# OakyWing-v0_2.net
KiCad netlist of a schematic drawn in EAGLE
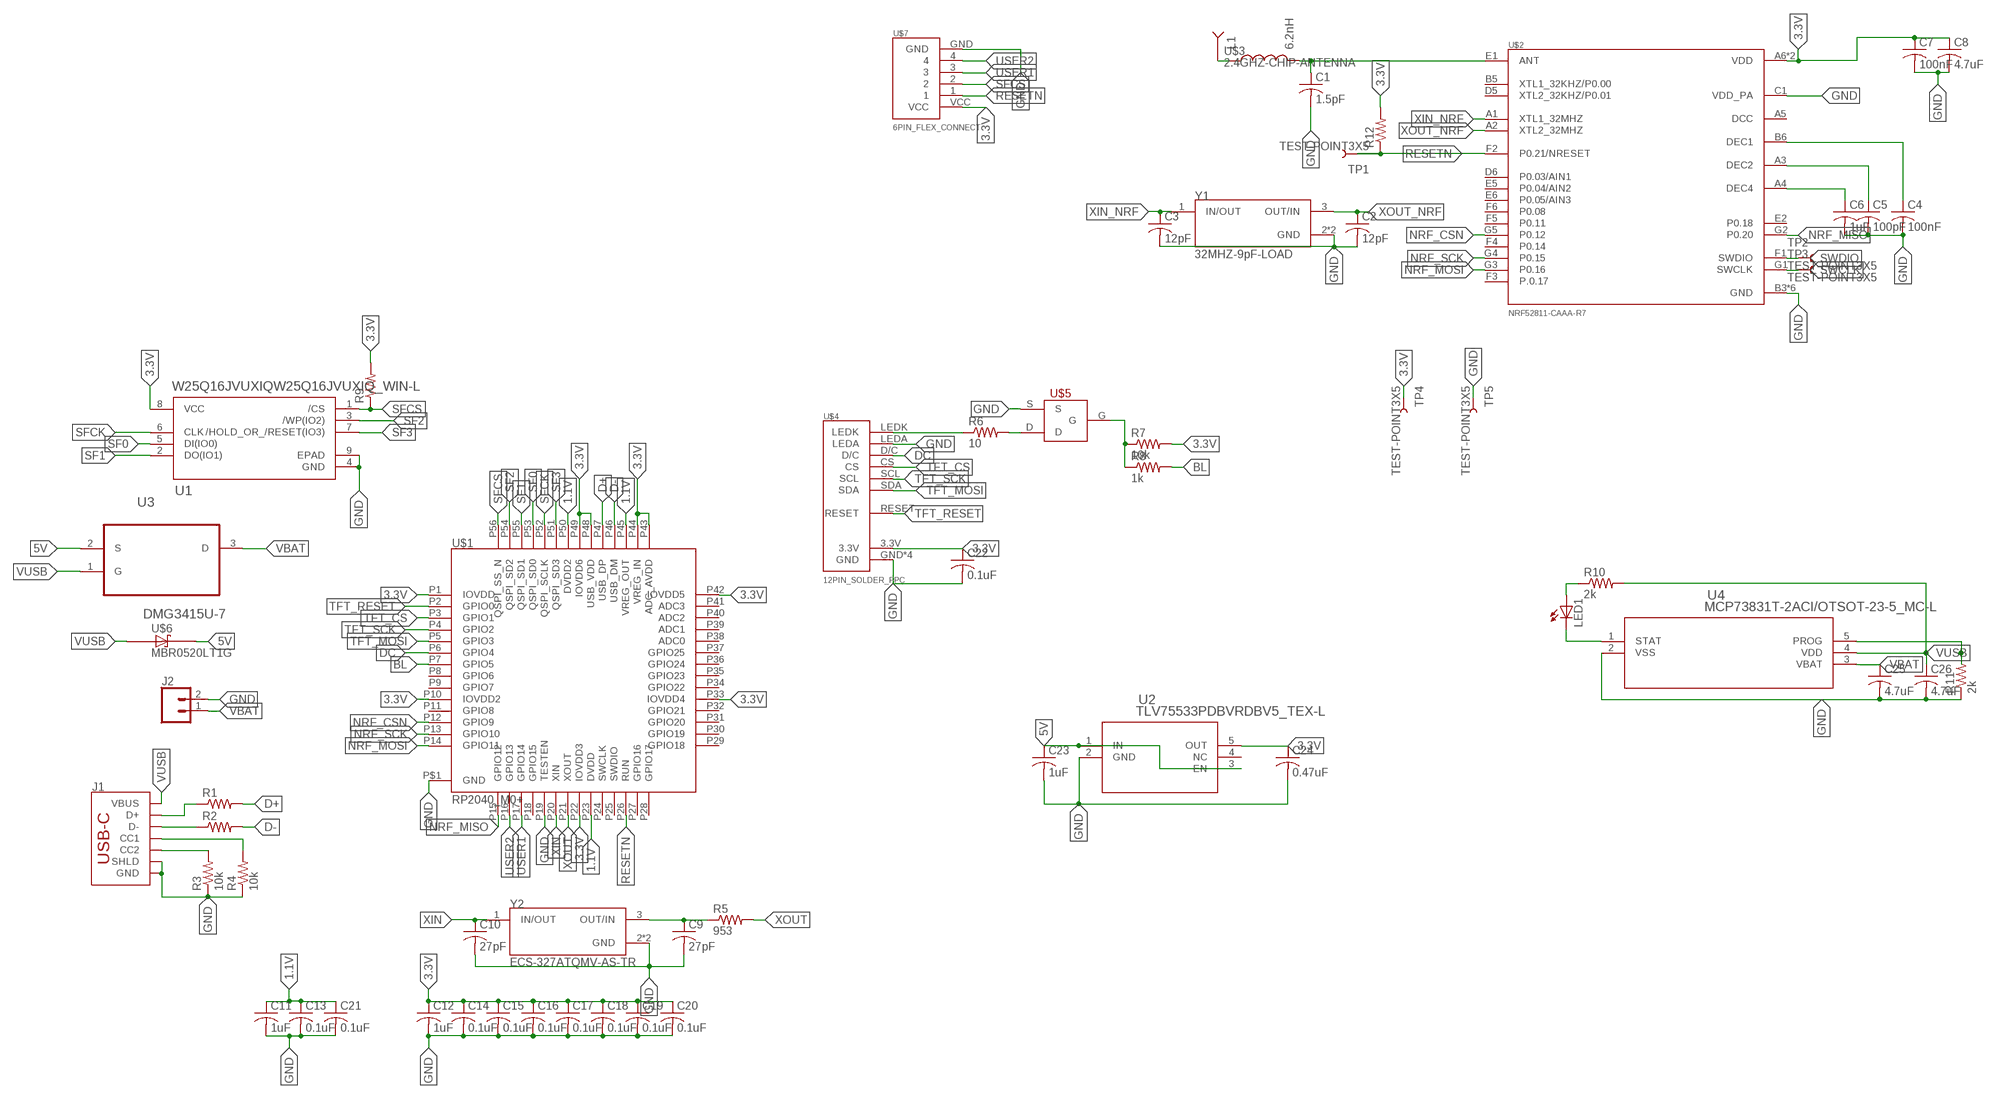
[diagram p0: schematic, sheet 1]

(export (version "E")
  (design (tool "Eeschema 10.0.6"))
  (components
    (comp (ref "C1")
      (value "1.5pF")
      (footprint "eagle-import:C0402")
      (libsource (lib "eagle-import") (part "rcl_334_C-USC0402"))
    )
    (comp (ref "C2")
      (value "12pF")
      (footprint "eagle-import:C0402")
      (libsource (lib "eagle-import") (part "rcl_334_C-USC0402"))
    )
    (comp (ref "C3")
      (value "12pF")
      (footprint "eagle-import:C0402")
      (libsource (lib "eagle-import") (part "C-USC0402"))
    )
    (comp (ref "C4")
      (value "100nF")
      (footprint "eagle-import:C0402")
      (libsource (lib "eagle-import") (part "rcl_334_C-USC0402"))
    )
    (comp (ref "C5")
      (value "100pF")
      (footprint "eagle-import:C0402")
      (libsource (lib "eagle-import") (part "rcl_334_C-USC0402"))
    )
    (comp (ref "C6")
      (value "1uF")
      (footprint "eagle-import:C0402")
      (libsource (lib "eagle-import") (part "rcl_334_C-USC0402"))
    )
    (comp (ref "C7")
      (value "100nF")
      (footprint "eagle-import:C0402")
      (libsource (lib "eagle-import") (part "rcl_334_C-USC0402"))
    )
    (comp (ref "C8")
      (value "4.7uF")
      (footprint "eagle-import:C0603")
      (libsource (lib "eagle-import") (part "rcl_334_C-USC0603"))
    )
    (comp (ref "C9")
      (value "27pF")
      (footprint "eagle-import:C0402")
      (libsource (lib "eagle-import") (part "C-USC0402"))
    )
    (comp (ref "C10")
      (value "27pF")
      (footprint "eagle-import:C0402")
      (libsource (lib "eagle-import") (part "C-USC0402"))
    )
    (comp (ref "C11")
      (value "1uF")
      (footprint "eagle-import:C0402")
      (libsource (lib "eagle-import") (part "C-USC0402"))
    )
    (comp (ref "C12")
      (value "1uF")
      (footprint "eagle-import:C0402")
      (libsource (lib "eagle-import") (part "C-USC0402"))
    )
    (comp (ref "C13")
      (value "0.1uF")
      (footprint "eagle-import:C0402")
      (libsource (lib "eagle-import") (part "C-USC0402"))
    )
    (comp (ref "C14")
      (value "0.1uF")
      (footprint "eagle-import:C0402")
      (libsource (lib "eagle-import") (part "C-USC0402"))
    )
    (comp (ref "C15")
      (value "0.1uF")
      (footprint "eagle-import:C0402")
      (libsource (lib "eagle-import") (part "C-USC0402"))
    )
    (comp (ref "C16")
      (value "0.1uF")
      (footprint "eagle-import:C0402")
      (libsource (lib "eagle-import") (part "C-USC0402"))
    )
    (comp (ref "C17")
      (value "0.1uF")
      (footprint "eagle-import:C0402")
      (libsource (lib "eagle-import") (part "C-USC0402"))
    )
    (comp (ref "C18")
      (value "0.1uF")
      (footprint "eagle-import:C0402")
      (libsource (lib "eagle-import") (part "C-USC0402"))
    )
    (comp (ref "C19")
      (value "0.1uF")
      (footprint "eagle-import:C0402")
      (libsource (lib "eagle-import") (part "C-USC0402"))
    )
    (comp (ref "C20")
      (value "0.1uF")
      (footprint "eagle-import:C0402")
      (libsource (lib "eagle-import") (part "C-USC0402"))
    )
    (comp (ref "C21")
      (value "0.1uF")
      (footprint "eagle-import:C0402")
      (libsource (lib "eagle-import") (part "C-USC0402"))
    )
    (comp (ref "C22")
      (value "0.1uF")
      (footprint "eagle-import:C0402")
      (libsource (lib "eagle-import") (part "rcl_334_C-USC0402"))
    )
    (comp (ref "C23")
      (value "1uF")
      (footprint "eagle-import:C0402")
      (libsource (lib "eagle-import") (part "rcl_334_C-USC0402"))
    )
    (comp (ref "C24")
      (value "0.47uF")
      (footprint "eagle-import:C0402")
      (libsource (lib "eagle-import") (part "rcl_334_C-USC0402"))
    )
    (comp (ref "C25")
      (value "4.7uF")
      (footprint "eagle-import:C0603")
      (libsource (lib "eagle-import") (part "rcl_334_C-USC0603"))
    )
    (comp (ref "C26")
      (value "4.7uF")
      (footprint "eagle-import:C0603")
      (libsource (lib "eagle-import") (part "rcl_334_C-USC0603"))
    )
    (comp (ref "J1")
      (value "USB_C_2-LAYER_PADS")
      (footprint "eagle-import:USB-C-16P-2LAYER-PADS")
      (libsource (lib "eagle-import") (part "USB_C_2-LAYER_PADS"))
    )
    (comp (ref "J2")
      (value "CONN_02")
      (footprint "eagle-import:1X02")
      (libsource (lib "eagle-import") (part "CONN_02"))
    )
    (comp (ref "L1")
      (value "6.2nH")
      (footprint "eagle-import:R0402")
      (libsource (lib "eagle-import") (part "INDUCTOR"))
    )
    (comp (ref "LED1")
      (value "LEDCHIP-LED0603")
      (footprint "eagle-import:CHIP-LED0603")
      (libsource (lib "eagle-import") (part "LEDCHIP-LED0603"))
    )
    (comp (ref "R1")
      (value "R-US_R0603")
      (footprint "eagle-import:R0603")
      (libsource (lib "eagle-import") (part "rcl_334_R-US_R0603"))
    )
    (comp (ref "R2")
      (value "R-US_R0603")
      (footprint "eagle-import:R0603")
      (libsource (lib "eagle-import") (part "rcl_334_R-US_R0603"))
    )
    (comp (ref "R3")
      (value "10k")
      (footprint "eagle-import:R0402")
      (libsource (lib "eagle-import") (part "R-US_R0402"))
    )
    (comp (ref "R4")
      (value "10k")
      (footprint "eagle-import:R0402")
      (libsource (lib "eagle-import") (part "R-US_R0402"))
    )
    (comp (ref "R5")
      (value "953")
      (footprint "eagle-import:R0402")
      (libsource (lib "eagle-import") (part "R-US_R0402"))
    )
    (comp (ref "R6")
      (value "10")
      (footprint "eagle-import:R0402")
      (libsource (lib "eagle-import") (part "rcl_334_R-US_R0402"))
    )
    (comp (ref "R7")
      (value "10k")
      (footprint "eagle-import:R0402")
      (libsource (lib "eagle-import") (part "rcl_334_R-US_R0402"))
    )
    (comp (ref "R8")
      (value "1k")
      (footprint "eagle-import:R0402")
      (libsource (lib "eagle-import") (part "rcl_334_R-US_R0402"))
    )
    (comp (ref "R9")
      (value "R-US_R0402")
      (footprint "eagle-import:R0402")
      (libsource (lib "eagle-import") (part "rcl_334_R-US_R0402"))
    )
    (comp (ref "R10")
      (value "2k")
      (footprint "eagle-import:R0603")
      (libsource (lib "eagle-import") (part "rcl_334_R-US_R0603"))
    )
    (comp (ref "R11")
      (value "2k")
      (footprint "eagle-import:R0603")
      (libsource (lib "eagle-import") (part "rcl_334_R-US_R0603"))
    )
    (comp (ref "R12")
      (value "R-US_R0402")
      (footprint "eagle-import:R0402")
      (libsource (lib "eagle-import") (part "rcl_334_R-US_R0402"))
    )
    (comp (ref "TP1")
      (value "TEST-POINT3X5")
      (footprint "eagle-import:PAD.03X.05")
      (libsource (lib "eagle-import") (part "TEST-POINT3X5"))
    )
    (comp (ref "TP2")
      (value "TEST-POINT3X5")
      (footprint "eagle-import:PAD.03X.05")
      (libsource (lib "eagle-import") (part "TEST-POINT3X5"))
    )
    (comp (ref "TP3")
      (value "TEST-POINT3X5")
      (footprint "eagle-import:PAD.03X.05")
      (libsource (lib "eagle-import") (part "TEST-POINT3X5"))
    )
    (comp (ref "TP4")
      (value "TEST-POINT3X5")
      (footprint "eagle-import:PAD.03X.05")
      (libsource (lib "eagle-import") (part "TEST-POINT3X5"))
    )
    (comp (ref "TP5")
      (value "TEST-POINT3X5")
      (footprint "eagle-import:PAD.03X.05")
      (libsource (lib "eagle-import") (part "TEST-POINT3X5"))
    )
    (comp (ref "U$1")
      (value "RP2040_M0+")
      (footprint "eagle-import:QFN-56")
      (libsource (lib "eagle-import") (part "RP2040_M0+"))
    )
    (comp (ref "U$2")
      (value "NRF52811-CAAA-R7")
      (footprint "eagle-import:WLCSP")
      (libsource (lib "eagle-import") (part "NRF52811-CAAA-R7"))
    )
    (comp (ref "U$3")
      (value "2.4GHZ-CHIP-ANTENNA")
      (footprint "eagle-import:2.4GHZ-ANT")
      (libsource (lib "eagle-import") (part "2.4GHZ-CHIP-ANTENNA"))
    )
    (comp (ref "U$4")
      (value "12PIN_SOLDER_FPC")
      (footprint "eagle-import:12PIN_SOLDER_FPC")
      (libsource (lib "eagle-import") (part "12PIN_SOLDER_FPC"))
    )
    (comp (ref "U$5")
      (value "DMN65D8L-7")
      (footprint "eagle-import:SOT-23")
      (libsource (lib "eagle-import") (part "DMN65D8L-7"))
    )
    (comp (ref "U$6")
      (value "MBR0520LT1G")
      (footprint "eagle-import:SOD3716X117(SOD-123)")
      (fields (field (name "MF") "ON Semiconductor"))
      (libsource (lib "eagle-import") (part "MBR0520LT1G"))
    )
    (comp (ref "U$7")
      (value "6PIN_FLEX_CONNECT")
      (footprint "eagle-import:6PIN_0.7MM")
      (libsource (lib "eagle-import") (part "6PIN_FLEX_CONNECT"))
    )
    (comp (ref "U1")
      (value "W25Q16JVUXIQW25Q16JVUXIQ_WIN-L")
      (footprint "eagle-import:W25Q16JVUXIQ_WIN-L")
      (fields
        (field (name "MANUFACTURER_PART_NUMBER") "W25Q16JVUXIQ")
        (field (name "COPYRIGHT") "Copyright (C) 2018 Accelerated Designs. All rights reserved")
      )
      (libsource (lib "eagle-import") (part "W25Q16JVUXIQW25Q16JVUXIQ_WIN-L"))
    )
    (comp (ref "U2")
      (value "TLV75533PDBVRDBV5_TEX-L")
      (footprint "eagle-import:DBV5_TEX-L")
      (fields
        (field (name "MANUFACTURER_PART_NUMBER") "TLV75533PDBVR")
        (field (name "COPYRIGHT") "Copyright (C) 2018 Accelerated Designs. All rights reserved")
      )
      (libsource (lib "eagle-import") (part "TLV75533PDBVRDBV5_TEX-L"))
    )
    (comp (ref "U3")
      (value "DMG3415U-7")
      (footprint "eagle-import:SOT95P240X105-3N")
      (fields (field (name "MF") "Diodes Inc."))
      (libsource (lib "eagle-import") (part "DMG3415U-7"))
    )
    (comp (ref "U4")
      (value "MCP73831T-2ACI/OTSOT-23-5_MC-L")
      (footprint "eagle-import:SOT-23-5_MC-L")
      (fields (field (name "MANUFACTURER_PART_NUMBER") "MCP73831T-2ACI/OT"))
      (libsource (lib "eagle-import") (part "MCP73831T-2ACI/OTSOT-23-5_MC-L"))
    )
    (comp (ref "Y1")
      (value "32MHZ-9pF-LOAD")
      (footprint "eagle-import:XTAL_ECS-327ATQMV-AS-TR")
      (fields
        (field (name "DIGI-KEY_PART_NUMBER") "XC2826CT-ND")
        (field (name "MF") "ECS Inc.")
        (field (name "MP") "ECS-327ATQMV-AS-TR")
      )
      (libsource (lib "eagle-import") (part "ECS-327ATQMV-AS-TR"))
    )
    (comp (ref "Y2")
      (value "ECS-327ATQMV-AS-TR")
      (footprint "eagle-import:XTAL_ECS-327ATQMV-AS-TR")
      (fields (field (name "DIGI-KEY_PART_NUMBER") "XC2826CT-ND") (field (name "MF") "ECS Inc."))
      (libsource (lib "eagle-import") (part "ECS-327ATQMV-AS-TR"))
    )
  )
  (nets
    (net (code "1") (name "1.1V") (class "Default")
      (node (ref "C11") (pin "1") (pinfunction "1_1") (pintype "passive"))
      (node (ref "C13") (pin "1") (pinfunction "1_1") (pintype "passive"))
      (node (ref "C21") (pin "1") (pinfunction "1_1") (pintype "passive"))
      (node (ref "U$1") (pin "P23") (pinfunction "DVDD_P23") (pintype "bidirectional"))
      (node (ref "U$1") (pin "P45") (pinfunction "VREG_OUT_P45") (pintype "bidirectional"))
      (node (ref "U$1") (pin "P50") (pinfunction "DVDD2_P50") (pintype "bidirectional"))
    )
    (net (code "2") (name "3.3V") (class "Default")
      (node (ref "C12") (pin "1") (pinfunction "1_1") (pintype "passive"))
      (node (ref "C14") (pin "1") (pinfunction "1_1") (pintype "passive"))
      (node (ref "C15") (pin "1") (pinfunction "1_1") (pintype "passive"))
      (node (ref "C16") (pin "1") (pinfunction "1_1") (pintype "passive"))
      (node (ref "C17") (pin "1") (pinfunction "1_1") (pintype "passive"))
      (node (ref "C18") (pin "1") (pinfunction "1_1") (pintype "passive"))
      (node (ref "C19") (pin "1") (pinfunction "1_1") (pintype "passive"))
      (node (ref "C20") (pin "1") (pinfunction "1_1") (pintype "passive"))
      (node (ref "C22") (pin "1") (pinfunction "1_1") (pintype "passive"))
      (node (ref "C24") (pin "1") (pinfunction "1_1") (pintype "passive"))
      (node (ref "C7") (pin "1") (pinfunction "1_1") (pintype "passive"))
      (node (ref "C8") (pin "1") (pinfunction "1_1") (pintype "passive"))
      (node (ref "R12") (pin "2") (pinfunction "2_2") (pintype "passive"))
      (node (ref "R7") (pin "2") (pinfunction "2_2") (pintype "passive"))
      (node (ref "R9") (pin "2") (pinfunction "2_2") (pintype "passive"))
      (node (ref "TP4") (pin "P$1") (pinfunction "1_P$1") (pintype "bidirectional"))
      (node (ref "U$1") (pin "P1") (pinfunction "IOVDD_P1") (pintype "bidirectional"))
      (node (ref "U$1") (pin "P10") (pinfunction "IOVDD2_P10") (pintype "bidirectional"))
      (node (ref "U$1") (pin "P22") (pinfunction "IOVDD3_P22") (pintype "bidirectional"))
      (node (ref "U$1") (pin "P33") (pinfunction "IOVDD4_P33") (pintype "bidirectional"))
      (node (ref "U$1") (pin "P42") (pinfunction "IOVDD5_P42") (pintype "bidirectional"))
      (node (ref "U$1") (pin "P43") (pinfunction "ADC_AVDD_P43") (pintype "bidirectional"))
      (node (ref "U$1") (pin "P44") (pinfunction "VREG_IN_P44") (pintype "bidirectional"))
      (node (ref "U$1") (pin "P48") (pinfunction "USB_VDD_P48") (pintype "bidirectional"))
      (node (ref "U$1") (pin "P49") (pinfunction "IOVDD6_P49") (pintype "bidirectional"))
      (node (ref "U$2") (pin "A6") (pinfunction "VDD_A6") (pintype "bidirectional"))
      (node (ref "U$2") (pin "G6") (pinfunction "VDD_G6") (pintype "bidirectional"))
      (node (ref "U$4") (pin "3.3V") (pinfunction "3.3V_3.3V") (pintype "bidirectional"))
      (node (ref "U$7") (pin "VCC") (pinfunction "VCC_VCC") (pintype "bidirectional"))
      (node (ref "U1") (pin "8") (pinfunction "VCC_8") (pintype "passive"))
      (node (ref "U2") (pin "5") (pinfunction "OUT_5") (pintype "output"))
    )
    (net (code "3") (name "5V") (class "Default")
      (node (ref "C23") (pin "1") (pinfunction "1_1") (pintype "passive"))
      (node (ref "U$6") (pin "1") (pinfunction "C_1") (pintype "passive"))
      (node (ref "U2") (pin "1") (pinfunction "IN_1") (pintype "input"))
      (node (ref "U2") (pin "3") (pinfunction "EN_3") (pintype "input"))
      (node (ref "U3") (pin "2") (pinfunction "S_2") (pintype "passive"))
    )
    (net (code "4") (name "BL") (class "Default")
      (node (ref "R8") (pin "2") (pinfunction "2_2") (pintype "passive"))
      (node (ref "U$1") (pin "P7") (pinfunction "GPIO5_P7") (pintype "bidirectional"))
    )
    (net (code "5") (name "D+") (class "Default")
      (node (ref "R1") (pin "2") (pinfunction "2_2") (pintype "passive"))
      (node (ref "U$1") (pin "P47") (pinfunction "USB_DP_P47") (pintype "bidirectional"))
    )
    (net (code "6") (name "D-") (class "Default")
      (node (ref "R2") (pin "2") (pinfunction "2_2") (pintype "passive"))
      (node (ref "U$1") (pin "P46") (pinfunction "USB_DM_P46") (pintype "bidirectional"))
    )
    (net (code "7") (name "DC") (class "Default")
      (node (ref "U$1") (pin "P6") (pinfunction "GPIO4_P6") (pintype "bidirectional"))
      (node (ref "U$4") (pin "D/C") (pinfunction "D/C_D/C") (pintype "bidirectional"))
    )
    (net (code "8") (name "GND") (class "Default")
      (node (ref "C1") (pin "2") (pinfunction "2_2") (pintype "passive"))
      (node (ref "C10") (pin "2") (pinfunction "2_2") (pintype "passive"))
      (node (ref "C11") (pin "2") (pinfunction "2_2") (pintype "passive"))
      (node (ref "C12") (pin "2") (pinfunction "2_2") (pintype "passive"))
      (node (ref "C13") (pin "2") (pinfunction "2_2") (pintype "passive"))
      (node (ref "C14") (pin "2") (pinfunction "2_2") (pintype "passive"))
      (node (ref "C15") (pin "2") (pinfunction "2_2") (pintype "passive"))
      (node (ref "C16") (pin "2") (pinfunction "2_2") (pintype "passive"))
      (node (ref "C17") (pin "2") (pinfunction "2_2") (pintype "passive"))
      (node (ref "C18") (pin "2") (pinfunction "2_2") (pintype "passive"))
      (node (ref "C19") (pin "2") (pinfunction "2_2") (pintype "passive"))
      (node (ref "C2") (pin "2") (pinfunction "2_2") (pintype "passive"))
      (node (ref "C20") (pin "2") (pinfunction "2_2") (pintype "passive"))
      (node (ref "C21") (pin "2") (pinfunction "2_2") (pintype "passive"))
      (node (ref "C22") (pin "2") (pinfunction "2_2") (pintype "passive"))
      (node (ref "C23") (pin "2") (pinfunction "2_2") (pintype "passive"))
      (node (ref "C24") (pin "2") (pinfunction "2_2") (pintype "passive"))
      (node (ref "C25") (pin "2") (pinfunction "2_2") (pintype "passive"))
      (node (ref "C26") (pin "2") (pinfunction "2_2") (pintype "passive"))
      (node (ref "C3") (pin "2") (pinfunction "2_2") (pintype "passive"))
      (node (ref "C4") (pin "2") (pinfunction "2_2") (pintype "passive"))
      (node (ref "C5") (pin "2") (pinfunction "2_2") (pintype "passive"))
      (node (ref "C6") (pin "2") (pinfunction "2_2") (pintype "passive"))
      (node (ref "C7") (pin "2") (pinfunction "2_2") (pintype "passive"))
      (node (ref "C8") (pin "2") (pinfunction "2_2") (pintype "passive"))
      (node (ref "C9") (pin "2") (pinfunction "2_2") (pintype "passive"))
      (node (ref "J1") (pin "GND") (pinfunction "GND_GND") (pintype "bidirectional"))
      (node (ref "J1") (pin "GND2") (pinfunction "GND_GND2") (pintype "bidirectional"))
      (node (ref "J1") (pin "P$1") (pinfunction "SHLD_P$1") (pintype "bidirectional"))
      (node (ref "J1") (pin "P$2") (pinfunction "SHLD_P$2") (pintype "bidirectional"))
      (node (ref "J1") (pin "P$3") (pinfunction "SHLD_P$3") (pintype "bidirectional"))
      (node (ref "J1") (pin "P$4") (pinfunction "SHLD_P$4") (pintype "bidirectional"))
      (node (ref "J1") (pin "SHLD1") (pinfunction "SHLD_SHLD1") (pintype "bidirectional"))
      (node (ref "J1") (pin "SHLD2") (pinfunction "SHLD_SHLD2") (pintype "bidirectional"))
      (node (ref "J1") (pin "SHLD3") (pinfunction "SHLD_SHLD3") (pintype "bidirectional"))
      (node (ref "J1") (pin "SHLD4") (pinfunction "SHLD_SHLD4") (pintype "bidirectional"))
      (node (ref "J2") (pin "2") (pinfunction "2_2") (pintype "passive"))
      (node (ref "R11") (pin "1") (pinfunction "1_1") (pintype "passive"))
      (node (ref "R3") (pin "1") (pinfunction "1_1") (pintype "passive"))
      (node (ref "R4") (pin "1") (pinfunction "1_1") (pintype "passive"))
      (node (ref "TP5") (pin "P$1") (pinfunction "1_P$1") (pintype "bidirectional"))
      (node (ref "U$1") (pin "P$1") (pinfunction "GND_P$1") (pintype "bidirectional"))
      (node (ref "U$1") (pin "P19") (pinfunction "TESTEN_P19") (pintype "bidirectional"))
      (node (ref "U$2") (pin "B3") (pinfunction "GND_B3") (pintype "bidirectional"))
      (node (ref "U$2") (pin "B4") (pinfunction "GND_B4") (pintype "bidirectional"))
      (node (ref "U$2") (pin "C1") (pinfunction "VDD_PA_C1") (pintype "bidirectional"))
      (node (ref "U$2") (pin "D3") (pinfunction "GND_D3") (pintype "bidirectional"))
      (node (ref "U$2") (pin "D4") (pinfunction "GND_D4") (pintype "bidirectional"))
      (node (ref "U$2") (pin "E3") (pinfunction "GND_E3") (pintype "bidirectional"))
      (node (ref "U$2") (pin "E4") (pinfunction "GND_E4") (pintype "bidirectional"))
      (node (ref "U$4") (pin "GND") (pinfunction "GND_GND") (pintype "bidirectional"))
      (node (ref "U$4") (pin "GND2") (pinfunction "GND_GND2") (pintype "bidirectional"))
      (node (ref "U$4") (pin "GND3") (pinfunction "GND_GND3") (pintype "bidirectional"))
      (node (ref "U$4") (pin "GND4") (pinfunction "GND_GND4") (pintype "bidirectional"))
      (node (ref "U$4") (pin "LEDA") (pinfunction "LEDA_LEDA") (pintype "bidirectional"))
      (node (ref "U$5") (pin "S") (pinfunction "S_S") (pintype "bidirectional"))
      (node (ref "U$7") (pin "GND") (pinfunction "GND_GND") (pintype "bidirectional"))
      (node (ref "U1") (pin "4") (pinfunction "GND_4") (pintype "passive"))
      (node (ref "U1") (pin "9") (pinfunction "EPAD_9") (pintype "passive"))
      (node (ref "U2") (pin "2") (pinfunction "GND_2") (pintype "power_in"))
      (node (ref "U4") (pin "2") (pinfunction "VSS_2") (pintype "passive"))
      (node (ref "Y1") (pin "2") (pinfunction "GND_2") (pintype "power_in"))
      (node (ref "Y1") (pin "4") (pinfunction "GND_4") (pintype "power_in"))
      (node (ref "Y2") (pin "2") (pinfunction "GND_2") (pintype "power_in"))
      (node (ref "Y2") (pin "4") (pinfunction "GND_4") (pintype "power_in"))
    )
    (net (code "9") (name "NRF_CSN") (class "Default")
      (node (ref "U$1") (pin "P12") (pinfunction "GPIO9_P12") (pintype "bidirectional"))
      (node (ref "U$2") (pin "G5") (pinfunction "P0.12_G5") (pintype "bidirectional"))
    )
    (net (code "10") (name "NRF_MISO") (class "Default")
      (node (ref "U$1") (pin "P15") (pinfunction "GPIO12_P15") (pintype "bidirectional"))
      (node (ref "U$2") (pin "G2") (pinfunction "P0.20_G2") (pintype "bidirectional"))
    )
    (net (code "11") (name "NRF_MOSI") (class "Default")
      (node (ref "U$1") (pin "P14") (pinfunction "GPIO11_P14") (pintype "bidirectional"))
      (node (ref "U$2") (pin "G3") (pinfunction "P0.16_G3") (pintype "bidirectional"))
    )
    (net (code "12") (name "NRF_SCK") (class "Default")
      (node (ref "U$1") (pin "P13") (pinfunction "GPIO10_P13") (pintype "bidirectional"))
      (node (ref "U$2") (pin "G4") (pinfunction "P0.15_G4") (pintype "bidirectional"))
    )
    (net (code "13") (name "Net-(J1-CC1)") (class "Default")
      (node (ref "J1") (pin "A5") (pinfunction "CC1_A5") (pintype "bidirectional"))
      (node (ref "R4") (pin "2") (pinfunction "2_2") (pintype "passive"))
    )
    (net (code "14") (name "Net-(J1-CC2)") (class "Default")
      (node (ref "J1") (pin "B5") (pinfunction "CC2_B5") (pintype "bidirectional"))
      (node (ref "R3") (pin "2") (pinfunction "2_2") (pintype "passive"))
    )
    (net (code "15") (name "Net-(J1-D+-PadA6)") (class "Default")
      (node (ref "J1") (pin "A6") (pinfunction "D+_A6") (pintype "bidirectional"))
      (node (ref "J1") (pin "B6") (pinfunction "D+_B6") (pintype "bidirectional"))
      (node (ref "R1") (pin "1") (pinfunction "1_1") (pintype "passive"))
    )
    (net (code "16") (name "Net-(J1-D--PadA7)") (class "Default")
      (node (ref "J1") (pin "A7") (pinfunction "D-_A7") (pintype "bidirectional"))
      (node (ref "J1") (pin "B7") (pinfunction "D-_B7") (pintype "bidirectional"))
      (node (ref "R2") (pin "1") (pinfunction "1_1") (pintype "passive"))
    )
    (net (code "17") (name "Net-(LED1-PadA)") (class "Default")
      (node (ref "LED1") (pin "A") (pinfunction "A_A") (pintype "passive"))
      (node (ref "R10") (pin "1") (pinfunction "1_1") (pintype "passive"))
    )
    (net (code "18") (name "Net-(R6-Pad1)") (class "Default")
      (node (ref "R6") (pin "1") (pinfunction "1_1") (pintype "passive"))
      (node (ref "U$4") (pin "LEDK") (pinfunction "LEDK_LEDK") (pintype "bidirectional"))
    )
    (net (code "19") (name "Net-(R6-Pad2)") (class "Default")
      (node (ref "R6") (pin "2") (pinfunction "2_2") (pintype "passive"))
      (node (ref "U$5") (pin "D") (pinfunction "D_D") (pintype "bidirectional"))
    )
    (net (code "20") (name "Net-(R7-Pad1)") (class "Default")
      (node (ref "R7") (pin "1") (pinfunction "1_1") (pintype "passive"))
      (node (ref "R8") (pin "1") (pinfunction "1_1") (pintype "passive"))
      (node (ref "U$5") (pin "G") (pinfunction "G_G") (pintype "bidirectional"))
    )
    (net (code "21") (name "Net-(U$2-ANT)") (class "Default")
      (node (ref "C1") (pin "1") (pinfunction "1_1") (pintype "passive"))
      (node (ref "L1") (pin "2") (pinfunction "2_2") (pintype "passive"))
      (node (ref "U$2") (pin "E1") (pinfunction "ANT_E1") (pintype "bidirectional"))
    )
    (net (code "22") (name "Net-(U$2-DEC1)") (class "Default")
      (node (ref "C4") (pin "1") (pinfunction "1_1") (pintype "passive"))
      (node (ref "U$2") (pin "B6") (pinfunction "DEC1_B6") (pintype "bidirectional"))
    )
    (net (code "23") (name "Net-(U$2-DEC2)") (class "Default")
      (node (ref "C5") (pin "1") (pinfunction "1_1") (pintype "passive"))
      (node (ref "U$2") (pin "A3") (pinfunction "DEC2_A3") (pintype "bidirectional"))
    )
    (net (code "24") (name "Net-(U$2-DEC4)") (class "Default")
      (node (ref "C6") (pin "1") (pinfunction "1_1") (pintype "passive"))
      (node (ref "U$2") (pin "A4") (pinfunction "DEC4_A4") (pintype "bidirectional"))
    )
    (net (code "25") (name "Net-(U$3-ANTENNA)") (class "Default")
      (node (ref "L1") (pin "1") (pinfunction "1_1") (pintype "passive"))
      (node (ref "U$3") (pin "2") (pinfunction "ANTENNA_2") (pintype "input"))
    )
    (net (code "26") (name "Net-(U4-PROG)") (class "Default")
      (node (ref "R11") (pin "2") (pinfunction "2_2") (pintype "passive"))
      (node (ref "U4") (pin "5") (pinfunction "PROG_5") (pintype "passive"))
    )
    (net (code "27") (name "Net-(U4-STAT)") (class "Default")
      (node (ref "LED1") (pin "C") (pinfunction "C_C") (pintype "passive"))
      (node (ref "U4") (pin "1") (pinfunction "STAT_1") (pintype "passive"))
    )
    (net (code "28") (name "Net-(Y2-OUT{slash}IN)") (class "Default")
      (node (ref "C9") (pin "1") (pinfunction "1_1") (pintype "passive"))
      (node (ref "R5") (pin "1") (pinfunction "1_1") (pintype "passive"))
      (node (ref "Y2") (pin "3") (pinfunction "OUT/IN_3") (pintype "bidirectional"))
    )
    (net (code "29") (name "RESETN") (class "Default")
      (node (ref "R12") (pin "1") (pinfunction "1_1") (pintype "passive"))
      (node (ref "TP1") (pin "P$1") (pinfunction "1_P$1") (pintype "bidirectional"))
      (node (ref "U$1") (pin "P26") (pinfunction "RUN_P26") (pintype "bidirectional"))
      (node (ref "U$2") (pin "F2") (pinfunction "P0.21/NRESET_F2") (pintype "bidirectional"))
      (node (ref "U$7") (pin "1") (pinfunction "1_1") (pintype "bidirectional"))
    )
    (net (code "30") (name "SF0") (class "Default")
      (node (ref "U$1") (pin "P53") (pinfunction "QSPI_SD0_P53") (pintype "bidirectional"))
      (node (ref "U1") (pin "5") (pinfunction "DI(IO0)_5") (pintype "passive"))
    )
    (net (code "31") (name "SF1") (class "Default")
      (node (ref "U$1") (pin "P55") (pinfunction "QSPI_SD1_P55") (pintype "bidirectional"))
      (node (ref "U1") (pin "2") (pinfunction "DO(IO1)_2") (pintype "passive"))
    )
    (net (code "32") (name "SF2") (class "Default")
      (node (ref "U$1") (pin "P54") (pinfunction "QSPI_SD2_P54") (pintype "bidirectional"))
      (node (ref "U1") (pin "3") (pinfunction "/WP(IO2)_3") (pintype "passive"))
    )
    (net (code "33") (name "SF3") (class "Default")
      (node (ref "U$1") (pin "P51") (pinfunction "QSPI_SD3_P51") (pintype "bidirectional"))
      (node (ref "U1") (pin "7") (pinfunction "/HOLD_OR_/RESET(IO3)_7") (pintype "passive"))
    )
    (net (code "34") (name "SFCK") (class "Default")
      (node (ref "U$1") (pin "P52") (pinfunction "QSPI_SCLK_P52") (pintype "bidirectional"))
      (node (ref "U1") (pin "6") (pinfunction "CLK_6") (pintype "passive"))
    )
    (net (code "35") (name "SFCS") (class "Default")
      (node (ref "R9") (pin "1") (pinfunction "1_1") (pintype "passive"))
      (node (ref "U$1") (pin "P56") (pinfunction "QSPI_SS_N_P56") (pintype "bidirectional"))
      (node (ref "U$7") (pin "2") (pinfunction "2_2") (pintype "bidirectional"))
      (node (ref "U1") (pin "1") (pinfunction "/CS_1") (pintype "passive"))
    )
    (net (code "36") (name "SWCLK") (class "Default")
      (node (ref "TP3") (pin "P$1") (pinfunction "1_P$1") (pintype "bidirectional"))
      (node (ref "U$2") (pin "G1") (pinfunction "SWCLK_G1") (pintype "bidirectional"))
    )
    (net (code "37") (name "SWDIO") (class "Default")
      (node (ref "TP2") (pin "P$1") (pinfunction "1_P$1") (pintype "bidirectional"))
      (node (ref "U$2") (pin "F1") (pinfunction "SWDIO_F1") (pintype "bidirectional"))
    )
    (net (code "38") (name "TFT_CS") (class "Default")
      (node (ref "U$1") (pin "P3") (pinfunction "GPIO1_P3") (pintype "bidirectional"))
      (node (ref "U$4") (pin "CS") (pinfunction "CS_CS") (pintype "bidirectional"))
    )
    (net (code "39") (name "TFT_MOSI") (class "Default")
      (node (ref "U$1") (pin "P5") (pinfunction "GPIO3_P5") (pintype "bidirectional"))
      (node (ref "U$4") (pin "SDA") (pinfunction "SDA_SDA") (pintype "bidirectional"))
    )
    (net (code "40") (name "TFT_RESET") (class "Default")
      (node (ref "U$1") (pin "P2") (pinfunction "GPIO0_P2") (pintype "bidirectional"))
      (node (ref "U$4") (pin "RESET") (pinfunction "RESET_RESET") (pintype "bidirectional"))
    )
    (net (code "41") (name "TFT_SCK") (class "Default")
      (node (ref "U$1") (pin "P4") (pinfunction "GPIO2_P4") (pintype "bidirectional"))
      (node (ref "U$4") (pin "SCL") (pinfunction "SCL_SCL") (pintype "bidirectional"))
    )
    (net (code "42") (name "USER1") (class "Default")
      (node (ref "U$1") (pin "P17") (pinfunction "GPIO14_P17") (pintype "bidirectional"))
      (node (ref "U$7") (pin "3") (pinfunction "3_3") (pintype "bidirectional"))
    )
    (net (code "43") (name "USER2") (class "Default")
      (node (ref "U$1") (pin "P16") (pinfunction "GPIO13_P16") (pintype "bidirectional"))
      (node (ref "U$7") (pin "4") (pinfunction "4_4") (pintype "bidirectional"))
    )
    (net (code "44") (name "VBAT") (class "Default")
      (node (ref "C25") (pin "1") (pinfunction "1_1") (pintype "passive"))
      (node (ref "J2") (pin "1") (pinfunction "1_1") (pintype "passive"))
      (node (ref "U3") (pin "3") (pinfunction "D_3") (pintype "output"))
      (node (ref "U4") (pin "3") (pinfunction "VBAT_3") (pintype "passive"))
    )
    (net (code "45") (name "VUSB") (class "Default")
      (node (ref "C26") (pin "1") (pinfunction "1_1") (pintype "passive"))
      (node (ref "J1") (pin "VBUS1") (pinfunction "VBUS_VBUS1") (pintype "bidirectional"))
      (node (ref "J1") (pin "VBUS2") (pinfunction "VBUS_VBUS2") (pintype "bidirectional"))
      (node (ref "R10") (pin "2") (pinfunction "2_2") (pintype "passive"))
      (node (ref "U$6") (pin "2") (pinfunction "A_2") (pintype "passive"))
      (node (ref "U3") (pin "1") (pinfunction "G_1") (pintype "power_in"))
      (node (ref "U4") (pin "4") (pinfunction "VDD_4") (pintype "passive"))
    )
    (net (code "46") (name "XIN") (class "Default")
      (node (ref "C10") (pin "1") (pinfunction "1_1") (pintype "passive"))
      (node (ref "U$1") (pin "P20") (pinfunction "XIN_P20") (pintype "bidirectional"))
      (node (ref "Y2") (pin "1") (pinfunction "IN/OUT_1") (pintype "bidirectional"))
    )
    (net (code "47") (name "XIN_NRF") (class "Default")
      (node (ref "C3") (pin "1") (pinfunction "1_1") (pintype "passive"))
      (node (ref "U$2") (pin "A1") (pinfunction "XTL1_32MHZ_A1") (pintype "bidirectional"))
      (node (ref "Y1") (pin "1") (pinfunction "IN/OUT_1") (pintype "bidirectional"))
    )
    (net (code "48") (name "XOUT") (class "Default")
      (node (ref "R5") (pin "2") (pinfunction "2_2") (pintype "passive"))
      (node (ref "U$1") (pin "P21") (pinfunction "XOUT_P21") (pintype "bidirectional"))
    )
    (net (code "49") (name "XOUT_NRF") (class "Default")
      (node (ref "C2") (pin "1") (pinfunction "1_1") (pintype "passive"))
      (node (ref "U$2") (pin "A2") (pinfunction "XTL2_32MHZ_A2") (pintype "bidirectional"))
      (node (ref "Y1") (pin "3") (pinfunction "OUT/IN_3") (pintype "bidirectional"))
    )
    (net (code "50") (name "unconnected-(U$1-ADC0-PadP38)") (class "Default")
      (node (ref "U$1") (pin "P38") (pinfunction "ADC0_P38") (pintype "bidirectional"))
    )
    (net (code "51") (name "unconnected-(U$1-ADC1-PadP39)") (class "Default")
      (node (ref "U$1") (pin "P39") (pinfunction "ADC1_P39") (pintype "bidirectional"))
    )
    (net (code "52") (name "unconnected-(U$1-ADC2-PadP40)") (class "Default")
      (node (ref "U$1") (pin "P40") (pinfunction "ADC2_P40") (pintype "bidirectional"))
    )
    (net (code "53") (name "unconnected-(U$1-ADC3-PadP41)") (class "Default")
      (node (ref "U$1") (pin "P41") (pinfunction "ADC3_P41") (pintype "bidirectional"))
    )
    (net (code "54") (name "unconnected-(U$1-GPIO6-PadP8)") (class "Default")
      (node (ref "U$1") (pin "P8") (pinfunction "GPIO6_P8") (pintype "bidirectional"))
    )
    (net (code "55") (name "unconnected-(U$1-GPIO7-PadP9)") (class "Default")
      (node (ref "U$1") (pin "P9") (pinfunction "GPIO7_P9") (pintype "bidirectional"))
    )
    (net (code "56") (name "unconnected-(U$1-GPIO8-PadP11)") (class "Default")
      (node (ref "U$1") (pin "P11") (pinfunction "GPIO8_P11") (pintype "bidirectional"))
    )
    (net (code "57") (name "unconnected-(U$1-GPIO15-PadP18)") (class "Default")
      (node (ref "U$1") (pin "P18") (pinfunction "GPIO15_P18") (pintype "bidirectional"))
    )
    (net (code "58") (name "unconnected-(U$1-GPIO16-PadP27)") (class "Default")
      (node (ref "U$1") (pin "P27") (pinfunction "GPIO16_P27") (pintype "bidirectional"))
    )
    (net (code "59") (name "unconnected-(U$1-GPIO17-PadP28)") (class "Default")
      (node (ref "U$1") (pin "P28") (pinfunction "GPIO17_P28") (pintype "bidirectional"))
    )
    (net (code "60") (name "unconnected-(U$1-GPIO18-PadP29)") (class "Default")
      (node (ref "U$1") (pin "P29") (pinfunction "GPIO18_P29") (pintype "bidirectional"))
    )
    (net (code "61") (name "unconnected-(U$1-GPIO19-PadP30)") (class "Default")
      (node (ref "U$1") (pin "P30") (pinfunction "GPIO19_P30") (pintype "bidirectional"))
    )
    (net (code "62") (name "unconnected-(U$1-GPIO20-PadP31)") (class "Default")
      (node (ref "U$1") (pin "P31") (pinfunction "GPIO20_P31") (pintype "bidirectional"))
    )
    (net (code "63") (name "unconnected-(U$1-GPIO21-PadP32)") (class "Default")
      (node (ref "U$1") (pin "P32") (pinfunction "GPIO21_P32") (pintype "bidirectional"))
    )
    (net (code "64") (name "unconnected-(U$1-GPIO22-PadP34)") (class "Default")
      (node (ref "U$1") (pin "P34") (pinfunction "GPIO22_P34") (pintype "bidirectional"))
    )
    (net (code "65") (name "unconnected-(U$1-GPIO23-PadP35)") (class "Default")
      (node (ref "U$1") (pin "P35") (pinfunction "GPIO23_P35") (pintype "bidirectional"))
    )
    (net (code "66") (name "unconnected-(U$1-GPIO24-PadP36)") (class "Default")
      (node (ref "U$1") (pin "P36") (pinfunction "GPIO24_P36") (pintype "bidirectional"))
    )
    (net (code "67") (name "unconnected-(U$1-GPIO25-PadP37)") (class "Default")
      (node (ref "U$1") (pin "P37") (pinfunction "GPIO25_P37") (pintype "bidirectional"))
    )
    (net (code "68") (name "unconnected-(U$1-SWCLK-PadP24)") (class "Default")
      (node (ref "U$1") (pin "P24") (pinfunction "SWCLK_P24") (pintype "bidirectional"))
    )
    (net (code "69") (name "unconnected-(U$1-SWDIO-PadP25)") (class "Default")
      (node (ref "U$1") (pin "P25") (pinfunction "SWDIO_P25") (pintype "bidirectional"))
    )
    (net (code "70") (name "unconnected-(U$2-DCC-PadA5)") (class "Default")
      (node (ref "U$2") (pin "A5") (pinfunction "DCC_A5") (pintype "bidirectional"))
    )
    (net (code "71") (name "unconnected-(U$2-P.0.17-PadF3)") (class "Default")
      (node (ref "U$2") (pin "F3") (pinfunction "P.0.17_F3") (pintype "bidirectional"))
    )
    (net (code "72") (name "unconnected-(U$2-P0.03{slash}AIN1-PadD6)") (class "Default")
      (node (ref "U$2") (pin "D6") (pinfunction "P0.03/AIN1_D6") (pintype "bidirectional"))
    )
    (net (code "73") (name "unconnected-(U$2-P0.04{slash}AIN2-PadE5)") (class "Default")
      (node (ref "U$2") (pin "E5") (pinfunction "P0.04/AIN2_E5") (pintype "bidirectional"))
    )
    (net (code "74") (name "unconnected-(U$2-P0.05{slash}AIN3-PadE6)") (class "Default")
      (node (ref "U$2") (pin "E6") (pinfunction "P0.05/AIN3_E6") (pintype "bidirectional"))
    )
    (net (code "75") (name "unconnected-(U$2-P0.08-PadF6)") (class "Default")
      (node (ref "U$2") (pin "F6") (pinfunction "P0.08_F6") (pintype "bidirectional"))
    )
    (net (code "76") (name "unconnected-(U$2-P0.11-PadF5)") (class "Default")
      (node (ref "U$2") (pin "F5") (pinfunction "P0.11_F5") (pintype "bidirectional"))
    )
    (net (code "77") (name "unconnected-(U$2-P0.14-PadF4)") (class "Default")
      (node (ref "U$2") (pin "F4") (pinfunction "P0.14_F4") (pintype "bidirectional"))
    )
    (net (code "78") (name "unconnected-(U$2-P0.18-PadE2)") (class "Default")
      (node (ref "U$2") (pin "E2") (pinfunction "P0.18_E2") (pintype "bidirectional"))
    )
    (net (code "79") (name "unconnected-(U$2-XTL1_32KHZ{slash}P0.00-PadB5)") (class "Default")
      (node (ref "U$2") (pin "B5") (pinfunction "XTL1_32KHZ/P0.00_B5") (pintype "bidirectional"))
    )
    (net (code "80") (name "unconnected-(U$2-XTL2_32KHZ{slash}P0.01-PadD5)") (class "Default")
      (node (ref "U$2") (pin "D5") (pinfunction "XTL2_32KHZ/P0.01_D5") (pintype "bidirectional"))
    )
    (net (code "81") (name "unconnected-(U2-NC-Pad4)") (class "Default")
      (node (ref "U2") (pin "4") (pinfunction "NC_4") (pintype "no_connect"))
    )
  )
)
